# atmospheric-1b1.net
KiCad netlist of a schematic drawn in EAGLE
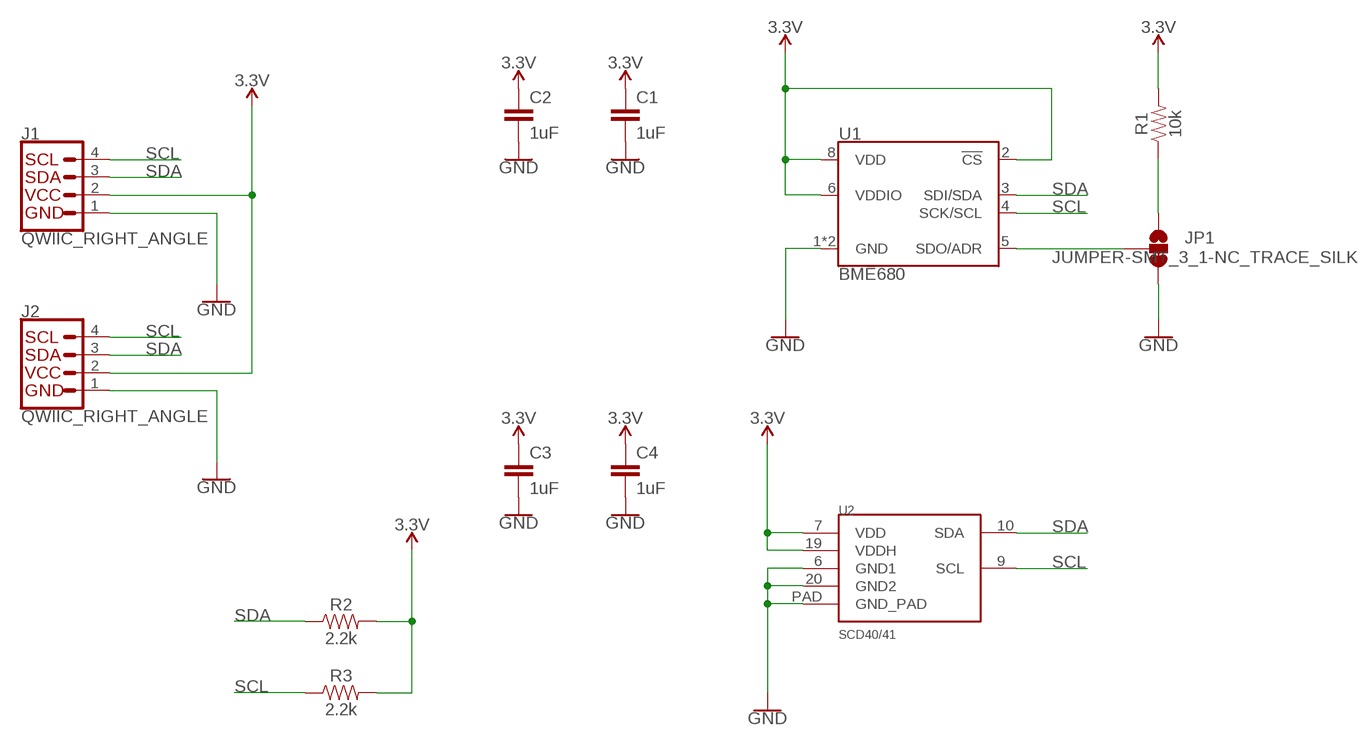
[diagram p0: schematic, sheet 1]

(export (version "E")
  (design (tool "Eeschema 10.0.6"))
  (components
    (comp (ref "C1")
      (value "1uF")
      (footprint "eagle-import:0603")
      (libsource (lib "eagle-import") (part "CAP-0603"))
    )
    (comp (ref "C2")
      (value "1uF")
      (footprint "eagle-import:0603")
      (libsource (lib "eagle-import") (part "CAP-0603"))
    )
    (comp (ref "C3")
      (value "1uF")
      (footprint "eagle-import:0603")
      (libsource (lib "eagle-import") (part "CAP-0603"))
    )
    (comp (ref "C4")
      (value "1uF")
      (footprint "eagle-import:0603")
      (libsource (lib "eagle-import") (part "CAP-0603"))
    )
    (comp (ref "J1")
      (value "QWIIC_RIGHT_ANGLE")
      (footprint "eagle-import:JST04_1MM_RA")
      (libsource (lib "eagle-import") (part "QWIIC_CONNECTORJS-1MM"))
    )
    (comp (ref "J2")
      (value "QWIIC_RIGHT_ANGLE")
      (footprint "eagle-import:JST04_1MM_RA")
      (libsource (lib "eagle-import") (part "QWIIC_CONNECTORJS-1MM"))
    )
    (comp (ref "JP1")
      (value "JUMPER-SMT_3_1-NC_TRACE_SILK")
      (footprint "eagle-import:SMT-JUMPER_3_1-NC_TRACE_SILK")
      (libsource (lib "eagle-import") (part "JUMPER-SMT_3_1-NC_TRACE_SILK"))
    )
    (comp (ref "R1")
      (value "10k")
      (footprint "eagle-import:0603")
      (libsource (lib "eagle-import") (part "RESISTOR0603"))
    )
    (comp (ref "R2")
      (value "2.2k")
      (footprint "eagle-import:0603")
      (libsource (lib "eagle-import") (part "RESISTOR0603"))
    )
    (comp (ref "R3")
      (value "2.2k")
      (footprint "eagle-import:0603")
      (libsource (lib "eagle-import") (part "RESISTOR0603"))
    )
    (comp (ref "U1")
      (value "BME680")
      (footprint "eagle-import:LGA3.0X3.0")
      (libsource (lib "eagle-import") (part "BME680-LGA"))
    )
    (comp (ref "U2")
      (value "SCD4X")
      (footprint "eagle-import:SCD4X")
      (libsource (lib "eagle-import") (part "SCD4X"))
    )
  )
  (nets
    (net (code "1") (name "/SCL") (class "Default")
      (node (ref "J1") (pin "4") (pinfunction "4_4") (pintype "passive"))
      (node (ref "J2") (pin "4") (pinfunction "4_4") (pintype "passive"))
      (node (ref "R3") (pin "1") (pinfunction "1_1") (pintype "passive"))
      (node (ref "U1") (pin "4") (pinfunction "SCK/SCL_4") (pintype "bidirectional"))
      (node (ref "U2") (pin "9") (pinfunction "SCL_9") (pintype "bidirectional"))
    )
    (net (code "2") (name "/SDA") (class "Default")
      (node (ref "J1") (pin "3") (pinfunction "3_3") (pintype "passive"))
      (node (ref "J2") (pin "3") (pinfunction "3_3") (pintype "passive"))
      (node (ref "R2") (pin "1") (pinfunction "1_1") (pintype "passive"))
      (node (ref "U1") (pin "3") (pinfunction "SDI/SDA_3") (pintype "bidirectional"))
      (node (ref "U2") (pin "10") (pinfunction "SDA_10") (pintype "bidirectional"))
    )
    (net (code "3") (name "3.3V") (class "Default")
      (node (ref "C1") (pin "1") (pinfunction "1_1") (pintype "passive"))
      (node (ref "C2") (pin "1") (pinfunction "1_1") (pintype "passive"))
      (node (ref "C3") (pin "1") (pinfunction "1_1") (pintype "passive"))
      (node (ref "C4") (pin "1") (pinfunction "1_1") (pintype "passive"))
      (node (ref "J1") (pin "2") (pinfunction "2_2") (pintype "power_in"))
      (node (ref "J2") (pin "2") (pinfunction "2_2") (pintype "power_in"))
      (node (ref "R1") (pin "2") (pinfunction "2_2") (pintype "passive"))
      (node (ref "R2") (pin "2") (pinfunction "2_2") (pintype "passive"))
      (node (ref "R3") (pin "2") (pinfunction "2_2") (pintype "passive"))
      (node (ref "U1") (pin "2") (pinfunction "~{CS}_2") (pintype "bidirectional"))
      (node (ref "U1") (pin "6") (pinfunction "VDDIO_6") (pintype "bidirectional"))
      (node (ref "U1") (pin "8") (pinfunction "VDD_8") (pintype "bidirectional"))
      (node (ref "U2") (pin "19") (pinfunction "VDDH_19") (pintype "bidirectional"))
      (node (ref "U2") (pin "7") (pinfunction "VDD_7") (pintype "bidirectional"))
    )
    (net (code "4") (name "GND") (class "Default")
      (node (ref "C1") (pin "2") (pinfunction "2_2") (pintype "passive"))
      (node (ref "C2") (pin "2") (pinfunction "2_2") (pintype "passive"))
      (node (ref "C3") (pin "2") (pinfunction "2_2") (pintype "passive"))
      (node (ref "C4") (pin "2") (pinfunction "2_2") (pintype "passive"))
      (node (ref "J1") (pin "1") (pinfunction "1_1") (pintype "power_in"))
      (node (ref "J2") (pin "1") (pinfunction "1_1") (pintype "power_in"))
      (node (ref "JP1") (pin "3") (pinfunction "3_3") (pintype "passive"))
      (node (ref "U1") (pin "1") (pinfunction "GND_1") (pintype "bidirectional"))
      (node (ref "U1") (pin "7") (pinfunction "GND_7") (pintype "bidirectional"))
      (node (ref "U2") (pin "20") (pinfunction "GND2_20") (pintype "bidirectional"))
      (node (ref "U2") (pin "6") (pinfunction "GND1_6") (pintype "bidirectional"))
      (node (ref "U2") (pin "PAD") (pinfunction "GND_PAD_PAD") (pintype "bidirectional"))
    )
    (net (code "5") (name "Net-(JP1-Pad1)") (class "Default")
      (node (ref "JP1") (pin "1") (pinfunction "1_1") (pintype "passive"))
      (node (ref "R1") (pin "1") (pinfunction "1_1") (pintype "passive"))
    )
    (net (code "6") (name "Net-(U1-SDO{slash}ADR)") (class "Default")
      (node (ref "JP1") (pin "2") (pinfunction "2_2") (pintype "passive"))
      (node (ref "U1") (pin "5") (pinfunction "SDO/ADR_5") (pintype "bidirectional"))
    )
  )
)
